# 6_shkb_upstream_con.net
KiCad netlist of a schematic drawn in Altium Designer
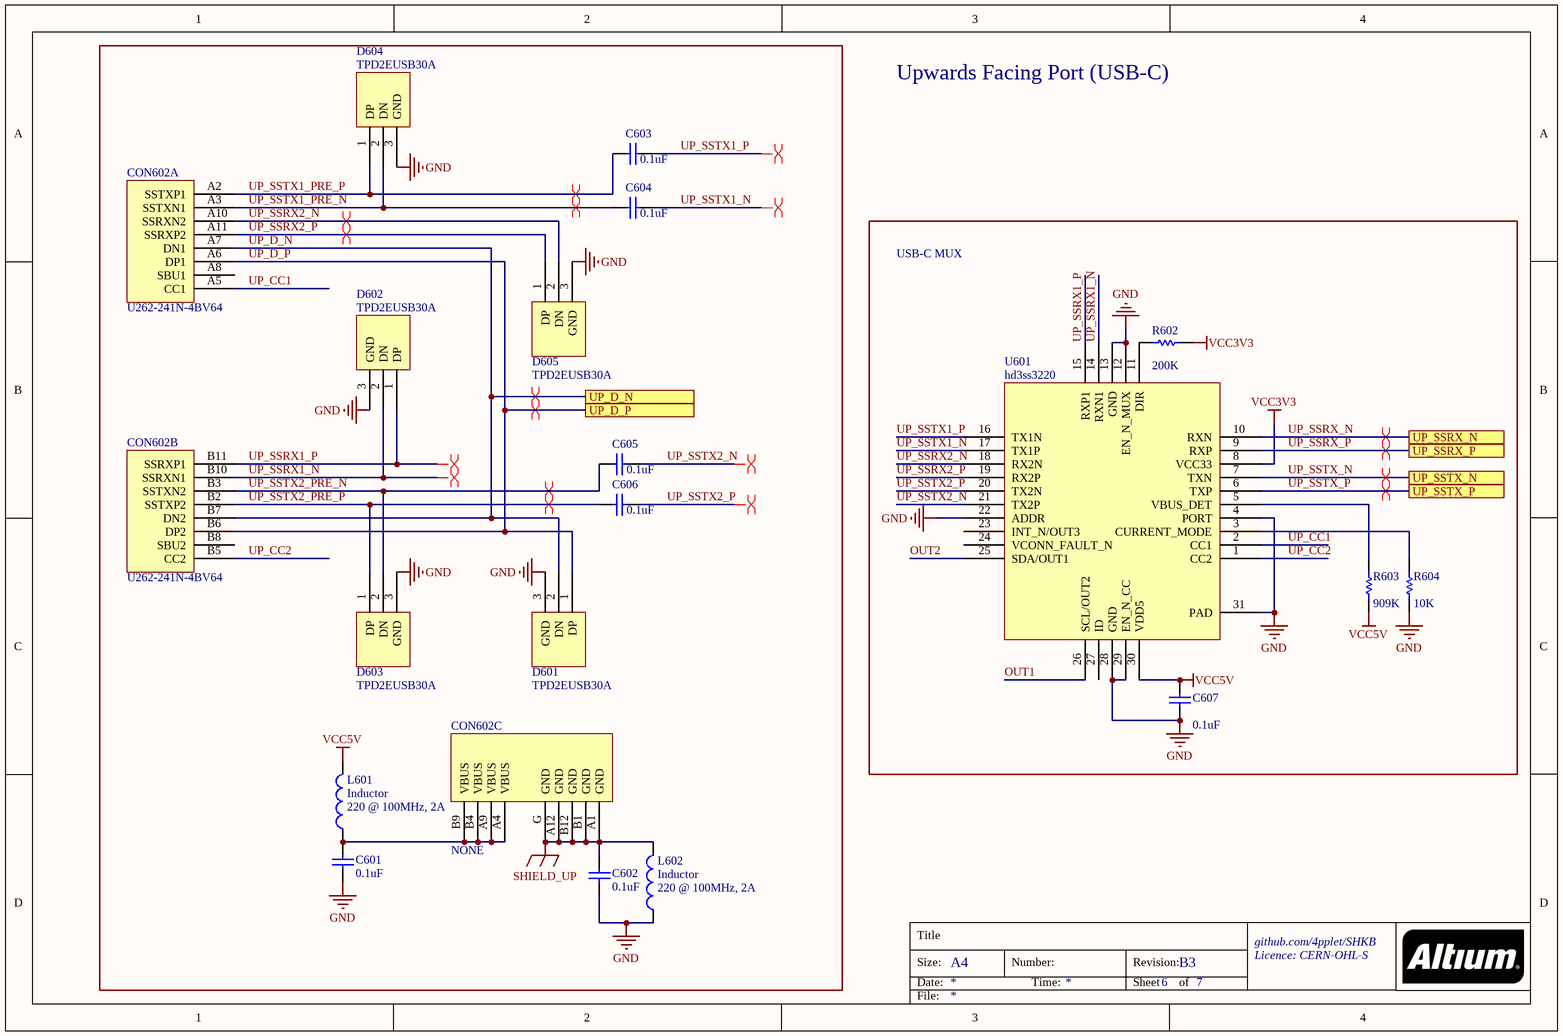
[diagram p0: 6_shkb_upstream_con.SchDoc]

(export (version "E")
  (design (tool "Eeschema 10.0.6"))
  (components
    (comp (ref "C601")
      (value "0.1uF")
      (footprint "C0603[1608]")
      (description "Capacitor")
      (fields (field (name "MFG") "KEMET") (field (name "LCSC PART #") "C14663"))
      (libsource (lib "Miscellaneous Devices") (part "Cap"))
    )
    (comp (ref "C602")
      (value "0.1uF")
      (footprint "C0603[1608]")
      (description "Capacitor")
      (fields (field (name "MFG") "KEMET") (field (name "LCSC PART #") "C14663"))
      (libsource (lib "Miscellaneous Devices") (part "Cap"))
    )
    (comp (ref "C603")
      (value "0.1uF")
      (footprint "C0402[1005]")
      (description "Capacitor")
      (fields (field (name "MFG") "KEMET") (field (name "LCSC PART #") "C1525"))
      (libsource (lib "Miscellaneous Devices") (part "Cap"))
    )
    (comp (ref "C604")
      (value "0.1uF")
      (footprint "C0402[1005]")
      (description "Capacitor")
      (fields (field (name "MFG") "KEMET") (field (name "LCSC PART #") "C1525"))
      (libsource (lib "Miscellaneous Devices") (part "Cap"))
    )
    (comp (ref "C605")
      (value "0.1uF")
      (footprint "C0402[1005]")
      (description "Capacitor")
      (fields (field (name "MFG") "KEMET") (field (name "LCSC PART #") "C1525"))
      (libsource (lib "Miscellaneous Devices") (part "Cap"))
    )
    (comp (ref "C606")
      (value "0.1uF")
      (footprint "C0402[1005]")
      (description "Capacitor")
      (fields (field (name "MFG") "KEMET") (field (name "LCSC PART #") "C1525"))
      (libsource (lib "Miscellaneous Devices") (part "Cap"))
    )
    (comp (ref "C607")
      (value "0.1uF")
      (footprint "C0603[1608]")
      (description "Capacitor")
      (fields (field (name "MFG") "KEMET") (field (name "LCSC PART #") "C14663"))
      (libsource (lib "Miscellaneous Devices") (part "Cap"))
    )
    (comp (ref "CON602")
      (value "for up to 1.6mm pcb")
      (footprint "XKB USB-C u262-241n-4bv64")
      (fields
        (field (name "JLC") "U262-241N-4BV64")
        (field (name "LCSC PART #") "C388660")
        (field (name "MRF.PART") "U262-241N-4BV64")
      )
      (libsource (lib "lib") (part "XKB USB-C u262-241n-4bv64"))
    )
    (comp (ref "D601")
      (value "TPD2EUSB30A")
      (footprint "TPD2EUSB30A")
      (fields
        (field (name "MFG") "Texas Instruments")
        (field (name "LCSC PART #") "C2844720")
        (field (name "MRF.PART") "TPD2EUSB30DRTR-TP")
      )
      (libsource (lib "") (part "TPD2EUSB30A_3"))
    )
    (comp (ref "D602")
      (value "TPD2EUSB30A")
      (footprint "TPD2EUSB30A")
      (fields
        (field (name "MFG") "Texas Instruments")
        (field (name "LCSC PART #") "C2844720")
        (field (name "MRF.PART") "TPD2EUSB30DRTR-TP")
      )
      (libsource (lib "") (part "TPD2EUSB30A_2"))
    )
    (comp (ref "D603")
      (value "TPD2EUSB30A")
      (footprint "TPD2EUSB30A")
      (fields
        (field (name "MFG") "Texas Instruments")
        (field (name "LCSC PART #") "C2844720")
        (field (name "MRF.PART") "TPD2EUSB30DRTR-TP")
      )
      (libsource (lib "") (part "TPD2EUSB30A_1"))
    )
    (comp (ref "D604")
      (value "TPD2EUSB30A")
      (footprint "TPD2EUSB30A")
      (fields
        (field (name "MFG") "Texas Instruments")
        (field (name "LCSC PART #") "C2844720")
        (field (name "MRF.PART") "TPD2EUSB30DRTR-TP")
      )
      (libsource (lib "lib") (part "TPD2EUSB30A"))
    )
    (comp (ref "D605")
      (value "TPD2EUSB30A")
      (footprint "TPD2EUSB30A")
      (fields
        (field (name "MFG") "Texas Instruments")
        (field (name "LCSC PART #") "C2844720")
        (field (name "MRF.PART") "TPD2EUSB30DRTR-TP")
      )
      (libsource (lib "") (part "TPD2EUSB30A_1"))
    )
    (comp (ref "L601")
      (value "Inductor")
      (footprint "L0603[1608]")
      (fields
        (field (name "ALTIUM_VALUE") "220 @ 100MHz, 2A")
        (field (name "MFG") "Murata Electronics North America")
        (field (name "LCSC PART #") "C85832")
        (field (name "MRF.PART") "BLM18KG331SN1D")
      )
      (libsource (lib "Miscellaneous Devices") (part "Inductor"))
    )
    (comp (ref "L602")
      (value "Inductor")
      (footprint "L0603[1608]")
      (fields
        (field (name "ALTIUM_VALUE") "220 @ 100MHz, 2A")
        (field (name "MFG") "Murata Electronics North America")
        (field (name "LCSC PART #") "C85832")
        (field (name "MRF.PART") "BLM18KG331SN1D")
      )
      (libsource (lib "Miscellaneous Devices") (part "Inductor"))
    )
    (comp (ref "R602")
      (value "200K")
      (footprint "R0603[1608]")
      (description "Resistor")
      (fields (field (name "MFG") "Vishay Dale") (field (name "LCSC PART #") "C25811"))
      (libsource (lib "Miscellaneous Devices") (part "Res1"))
    )
    (comp (ref "R603")
      (value "909K")
      (footprint "R0603[1608]")
      (description "Resistor")
      (fields (field (name "MFG") "Vishay Dale") (field (name "LCSC PART #") "C22935"))
      (libsource (lib "Miscellaneous Devices") (part "Res1"))
    )
    (comp (ref "R604")
      (value "10K")
      (footprint "R0603[1608]")
      (description "Resistor")
      (fields (field (name "MFG") "Vishay Dale") (field (name "LCSC PART #") "C25804"))
      (libsource (lib "Miscellaneous Devices") (part "Res1"))
    )
    (comp (ref "U601")
      (value "hd3ss3220")
      (footprint "hd3ss3220")
      (fields
        (field (name "MFG") "Texas Instruments")
        (field (name "LCSC PART #") "C165155")
        (field (name "MRF.PART") "HD3SS3220RNHR")
      )
      (libsource (lib "lib") (part "hd3ss3220"))
    )
  )
  (nets
    (net (code "1") (name "/OUT1") (class "Default")
      (node (ref "U601") (pin "26") (pinfunction "SCL/OUT2_26") (pintype "passive"))
    )
    (net (code "2") (name "/OUT2") (class "Default")
      (node (ref "U601") (pin "25") (pinfunction "SDA/OUT1_25") (pintype "passive"))
    )
    (net (code "3") (name "/UP_CC1") (class "Default")
      (node (ref "CON602") (pin "A5") (pinfunction "CC1_A5") (pintype "passive"))
      (node (ref "U601") (pin "2") (pinfunction "CC1_2") (pintype "passive"))
    )
    (net (code "4") (name "/UP_CC2") (class "Default")
      (node (ref "CON602") (pin "B5") (pinfunction "CC2_B5") (pintype "passive"))
      (node (ref "U601") (pin "1") (pinfunction "CC2_1") (pintype "passive"))
    )
    (net (code "5") (name "/UP_D_N") (class "Default")
      (node (ref "CON602") (pin "A7") (pinfunction "DN1_A7") (pintype "passive"))
      (node (ref "CON602") (pin "B7") (pinfunction "DN2_B7") (pintype "passive"))
      (node (ref "D601") (pin "2") (pinfunction "DN_2") (pintype "passive"))
    )
    (net (code "6") (name "/UP_D_P") (class "Default")
      (node (ref "CON602") (pin "A6") (pinfunction "DP1_A6") (pintype "passive"))
      (node (ref "CON602") (pin "B6") (pinfunction "DP2_B6") (pintype "passive"))
      (node (ref "D601") (pin "1") (pinfunction "DP_1") (pintype "passive"))
    )
    (net (code "7") (name "/UP_SSRX1_N") (class "Default")
      (node (ref "CON602") (pin "B10") (pinfunction "SSRXN1_B10") (pintype "passive"))
      (node (ref "D602") (pin "2") (pinfunction "DN_2") (pintype "passive"))
      (node (ref "U601") (pin "14") (pinfunction "RXN1_14") (pintype "passive"))
    )
    (net (code "8") (name "/UP_SSRX1_P") (class "Default")
      (node (ref "CON602") (pin "B11") (pinfunction "SSRXP1_B11") (pintype "passive"))
      (node (ref "D602") (pin "1") (pinfunction "DP_1") (pintype "passive"))
      (node (ref "U601") (pin "15") (pinfunction "RXP1_15") (pintype "passive"))
    )
    (net (code "9") (name "/UP_SSRX2_N") (class "Default")
      (node (ref "CON602") (pin "A10") (pinfunction "SSRXN2_A10") (pintype "passive"))
      (node (ref "D605") (pin "2") (pinfunction "DN_2") (pintype "passive"))
      (node (ref "U601") (pin "18") (pinfunction "RX2N_18") (pintype "passive"))
    )
    (net (code "10") (name "/UP_SSRX2_P") (class "Default")
      (node (ref "CON602") (pin "A11") (pinfunction "SSRXP2_A11") (pintype "passive"))
      (node (ref "D605") (pin "1") (pinfunction "DP_1") (pintype "passive"))
      (node (ref "U601") (pin "19") (pinfunction "RX2P_19") (pintype "passive"))
    )
    (net (code "11") (name "/UP_SSRX_N") (class "Default")
      (node (ref "U601") (pin "10") (pinfunction "RXN_10") (pintype "passive"))
    )
    (net (code "12") (name "/UP_SSRX_P") (class "Default")
      (node (ref "U601") (pin "9") (pinfunction "RXP_9") (pintype "passive"))
    )
    (net (code "13") (name "/UP_SSTX1_N") (class "Default")
      (node (ref "C604") (pin "2") (pinfunction "2_2") (pintype "passive"))
      (node (ref "U601") (pin "17") (pinfunction "TX1P_17") (pintype "passive"))
    )
    (net (code "14") (name "/UP_SSTX1_P") (class "Default")
      (node (ref "C603") (pin "2") (pinfunction "2_2") (pintype "passive"))
      (node (ref "U601") (pin "16") (pinfunction "TX1N_16") (pintype "passive"))
    )
    (net (code "15") (name "/UP_SSTX1_PRE_N") (class "Default")
      (node (ref "C604") (pin "1") (pinfunction "1_1") (pintype "passive"))
      (node (ref "CON602") (pin "A3") (pinfunction "SSTXN1_A3") (pintype "passive"))
      (node (ref "D604") (pin "2") (pinfunction "DN_2") (pintype "passive"))
    )
    (net (code "16") (name "/UP_SSTX1_PRE_P") (class "Default")
      (node (ref "C603") (pin "1") (pinfunction "1_1") (pintype "passive"))
      (node (ref "CON602") (pin "A2") (pinfunction "SSTXP1_A2") (pintype "passive"))
      (node (ref "D604") (pin "1") (pinfunction "DP_1") (pintype "passive"))
    )
    (net (code "17") (name "/UP_SSTX2_N") (class "Default")
      (node (ref "C605") (pin "2") (pinfunction "2_2") (pintype "passive"))
      (node (ref "U601") (pin "21") (pinfunction "TX2P_21") (pintype "passive"))
    )
    (net (code "18") (name "/UP_SSTX2_P") (class "Default")
      (node (ref "C606") (pin "2") (pinfunction "2_2") (pintype "passive"))
      (node (ref "U601") (pin "20") (pinfunction "TX2N_20") (pintype "passive"))
    )
    (net (code "19") (name "/UP_SSTX2_PRE_N") (class "Default")
      (node (ref "C605") (pin "1") (pinfunction "1_1") (pintype "passive"))
      (node (ref "CON602") (pin "B3") (pinfunction "SSTXN2_B3") (pintype "passive"))
      (node (ref "D603") (pin "2") (pinfunction "DN_2") (pintype "passive"))
    )
    (net (code "20") (name "/UP_SSTX2_PRE_P") (class "Default")
      (node (ref "C606") (pin "1") (pinfunction "1_1") (pintype "passive"))
      (node (ref "CON602") (pin "B2") (pinfunction "SSTXP2_B2") (pintype "passive"))
      (node (ref "D603") (pin "1") (pinfunction "DP_1") (pintype "passive"))
    )
    (net (code "21") (name "/UP_SSTX_N") (class "Default")
      (node (ref "U601") (pin "7") (pinfunction "TXN_7") (pintype "passive"))
    )
    (net (code "22") (name "/UP_SSTX_P") (class "Default")
      (node (ref "U601") (pin "6") (pinfunction "TXP_6") (pintype "passive"))
    )
    (net (code "23") (name "GND") (class "Default")
      (node (ref "C601") (pin "1") (pinfunction "1_1") (pintype "passive"))
      (node (ref "C602") (pin "1") (pinfunction "1_1") (pintype "passive"))
      (node (ref "C607") (pin "1") (pinfunction "1_1") (pintype "passive"))
      (node (ref "D601") (pin "3") (pinfunction "GND_3") (pintype "passive"))
      (node (ref "D602") (pin "3") (pinfunction "GND_3") (pintype "passive"))
      (node (ref "D603") (pin "3") (pinfunction "GND_3") (pintype "passive"))
      (node (ref "D604") (pin "3") (pinfunction "GND_3") (pintype "passive"))
      (node (ref "D605") (pin "3") (pinfunction "GND_3") (pintype "passive"))
      (node (ref "L602") (pin "1") (pinfunction "1_1") (pintype "passive"))
      (node (ref "R604") (pin "2") (pinfunction "2_2") (pintype "passive"))
      (node (ref "U601") (pin "12") (pinfunction "EN_N_MUX_12") (pintype "passive"))
      (node (ref "U601") (pin "13") (pinfunction "GND_13") (pintype "passive"))
      (node (ref "U601") (pin "22") (pinfunction "ADDR_22") (pintype "passive"))
      (node (ref "U601") (pin "28") (pinfunction "GND_28") (pintype "passive"))
      (node (ref "U601") (pin "29") (pinfunction "EN_N_CC_29") (pintype "passive"))
      (node (ref "U601") (pin "31") (pinfunction "PAD_31") (pintype "passive"))
      (node (ref "U601") (pin "4") (pinfunction "PORT_4") (pintype "passive"))
    )
    (net (code "24") (name "Net-(C601-Pad2)") (class "Default")
      (node (ref "C601") (pin "2") (pinfunction "2_2") (pintype "passive"))
      (node (ref "CON602") (pin "A4") (pinfunction "VBUS_A4") (pintype "passive"))
      (node (ref "CON602") (pin "A9") (pinfunction "VBUS_A9") (pintype "passive"))
      (node (ref "CON602") (pin "B4") (pinfunction "VBUS_B4") (pintype "passive"))
      (node (ref "CON602") (pin "B9") (pinfunction "VBUS_B9") (pintype "passive"))
      (node (ref "L601") (pin "1") (pinfunction "1_1") (pintype "passive"))
    )
    (net (code "25") (name "Net-(U601-CURRENT_MODE)") (class "Default")
      (node (ref "R604") (pin "1") (pinfunction "1_1") (pintype "passive"))
      (node (ref "U601") (pin "3") (pinfunction "CURRENT_MODE_3") (pintype "passive"))
    )
    (net (code "26") (name "Net-(U601-DIR)") (class "Default")
      (node (ref "R602") (pin "1") (pinfunction "1_1") (pintype "passive"))
      (node (ref "U601") (pin "11") (pinfunction "DIR_11") (pintype "passive"))
    )
    (net (code "27") (name "Net-(U601-VBUS_DET)") (class "Default")
      (node (ref "R603") (pin "1") (pinfunction "1_1") (pintype "passive"))
      (node (ref "U601") (pin "5") (pinfunction "VBUS_DET_5") (pintype "passive"))
    )
    (net (code "28") (name "SHIELD_UP") (class "Default")
      (node (ref "C602") (pin "2") (pinfunction "2_2") (pintype "passive"))
      (node (ref "CON602") (pin "A1") (pinfunction "GND_A1") (pintype "passive"))
      (node (ref "CON602") (pin "A12") (pinfunction "GND_A12") (pintype "passive"))
      (node (ref "CON602") (pin "B1") (pinfunction "GND_B1") (pintype "passive"))
      (node (ref "CON602") (pin "B12") (pinfunction "GND_B12") (pintype "passive"))
      (node (ref "CON602") (pin "G") (pinfunction "GND_G") (pintype "passive"))
      (node (ref "L602") (pin "2") (pinfunction "2_2") (pintype "passive"))
    )
    (net (code "29") (name "VCC3V3") (class "Default")
      (node (ref "R602") (pin "2") (pinfunction "2_2") (pintype "passive"))
      (node (ref "U601") (pin "8") (pinfunction "VCC33_8") (pintype "passive"))
    )
    (net (code "30") (name "VCC5V") (class "Default")
      (node (ref "C607") (pin "2") (pinfunction "2_2") (pintype "passive"))
      (node (ref "L601") (pin "2") (pinfunction "2_2") (pintype "passive"))
      (node (ref "R603") (pin "2") (pinfunction "2_2") (pintype "passive"))
      (node (ref "U601") (pin "30") (pinfunction "VDD5_30") (pintype "passive"))
    )
    (net (code "31") (name "unconnected-(CON602A-SBU1-PadA8)") (class "Default")
      (node (ref "CON602") (pin "A8") (pinfunction "SBU1_A8") (pintype "passive"))
    )
    (net (code "32") (name "unconnected-(CON602B-SBU2-PadB8)") (class "Default")
      (node (ref "CON602") (pin "B8") (pinfunction "SBU2_B8") (pintype "passive"))
    )
    (net (code "33") (name "unconnected-(U601-ID-Pad27)") (class "Default")
      (node (ref "U601") (pin "27") (pinfunction "ID_27") (pintype "passive"))
    )
    (net (code "34") (name "unconnected-(U601-INT_N{slash}OUT3-Pad23)") (class "Default")
      (node (ref "U601") (pin "23") (pinfunction "INT_N/OUT3_23") (pintype "passive"))
    )
    (net (code "35") (name "unconnected-(U601-VCONN_FAULT_N-Pad24)") (class "Default")
      (node (ref "U601") (pin "24") (pinfunction "VCONN_FAULT_N_24") (pintype "passive"))
    )
  )
)
